# serboRGB.net
KiCad netlist of a schematic drawn in EAGLE
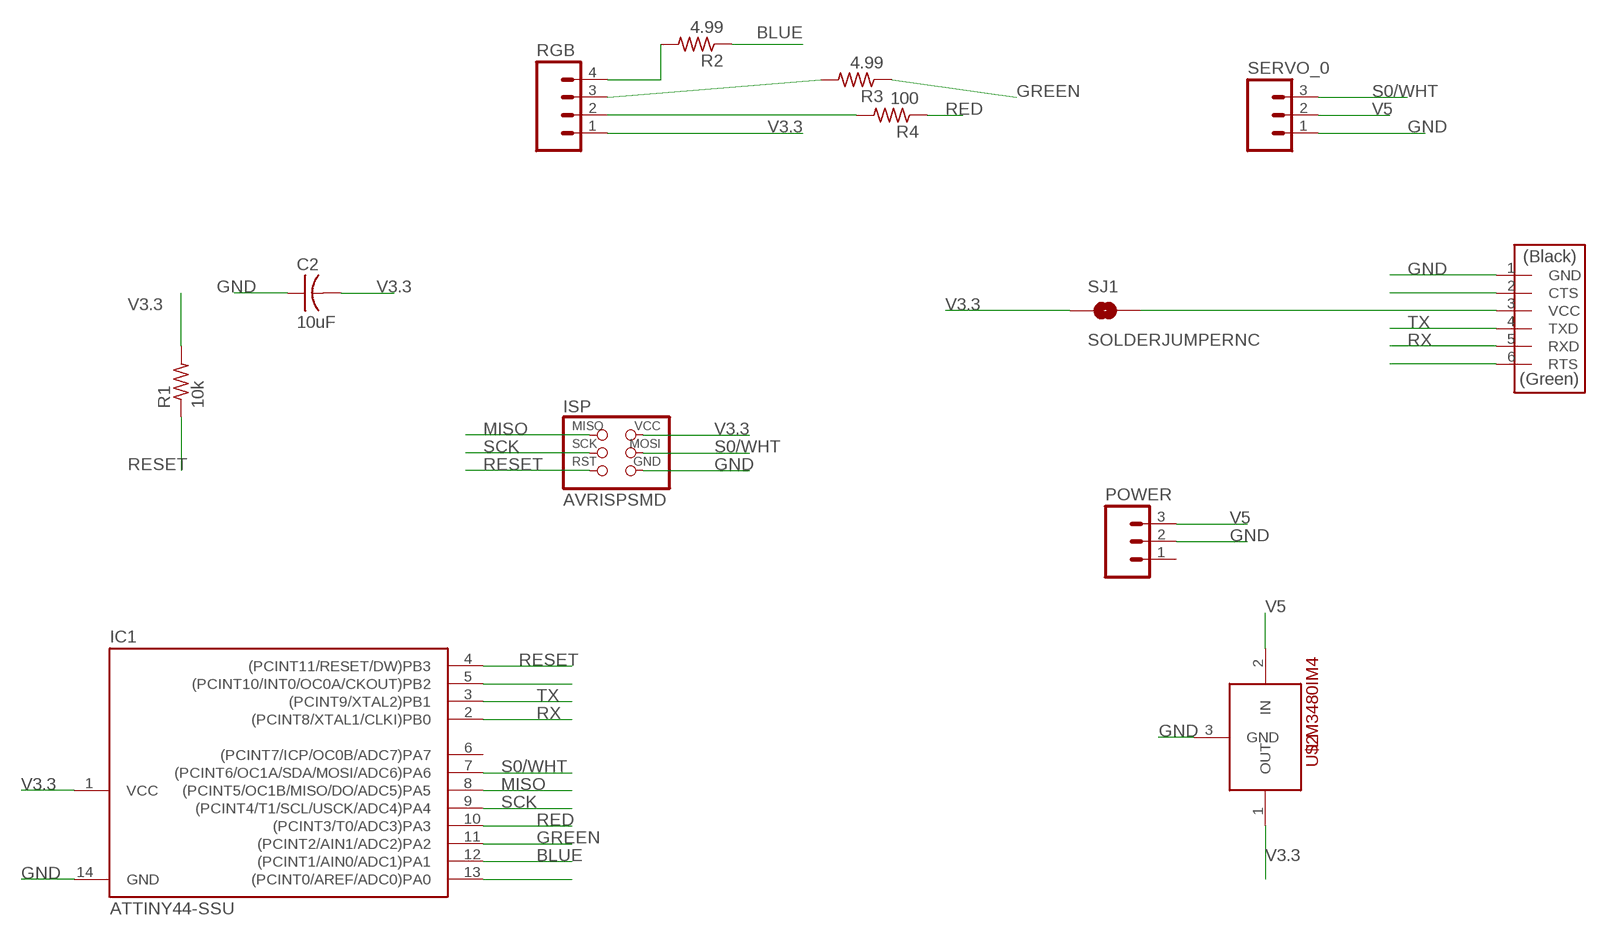
[diagram p0: schematic, sheet 1]

(export (version "E")
  (design (tool "Eeschema 10.0.6"))
  (components
    (comp (ref "C2")
      (value "10uF")
      (footprint "eagle-import:C1206FAB")
      (libsource (lib "eagle-import") (part "CAP-US1206FAB"))
    )
    (comp (ref "IC1")
      (value "ATTINY44-SSU")
      (footprint "eagle-import:SOIC14")
      (libsource (lib "eagle-import") (part "ATTINY44-SSU"))
    )
    (comp (ref "ISP")
      (value "AVRISPSMD")
      (footprint "eagle-import:2X03SMD")
      (libsource (lib "eagle-import") (part "AVRISPSMD"))
    )
    (comp (ref "POWER")
      (value "M03SMD_RA_MALE_POST")
      (footprint "eagle-import:1X03_SMD_RA_MALE_POST")
      (libsource (lib "eagle-import") (part "M03SMD_RA_MALE_POST"))
    )
    (comp (ref "R1")
      (value "10k")
      (footprint "eagle-import:1206")
      (libsource (lib "eagle-import") (part "RESISTOR1206"))
    )
    (comp (ref "R2")
      (value "4.99")
      (footprint "eagle-import:1206")
      (libsource (lib "eagle-import") (part "RESISTOR1206"))
    )
    (comp (ref "R3")
      (value "4.99")
      (footprint "eagle-import:1206")
      (libsource (lib "eagle-import") (part "RESISTOR1206"))
    )
    (comp (ref "R4")
      (value "100")
      (footprint "eagle-import:1206")
      (libsource (lib "eagle-import") (part "RESISTOR1206"))
    )
    (comp (ref "RGB")
      (value "M04SMD")
      (footprint "eagle-import:1X04-SMD")
      (libsource (lib "eagle-import") (part "M04SMD"))
    )
    (comp (ref "SERVO_0")
      (value "M03SMD_RA_MALE_POST")
      (footprint "eagle-import:1X03_SMD_RA_MALE_POST")
      (libsource (lib "eagle-import") (part "M03SMD_RA_MALE_POST"))
    )
    (comp (ref "SJ1")
      (value "SOLDERJUMPERNC")
      (footprint "eagle-import:SJ_2S")
      (libsource (lib "eagle-import") (part "SOLDERJUMPERNC"))
    )
    (comp (ref "U$1")
      (value "FTDI-SMD-HEADER")
      (footprint "eagle-import:1X06SMD")
      (libsource (lib "eagle-import") (part "FTDI-SMD-HEADER"))
    )
    (comp (ref "U$2")
      (value "LM3480IM4")
      (footprint "eagle-import:SOT23-3")
      (libsource (lib "eagle-import") (part "LM3480IM4"))
    )
  )
  (nets
    (net (code "1") (name "/BLUE") (class "Default")
      (node (ref "IC1") (pin "12") (pinfunction "(PCINT1/AIN0/ADC1)PA1_12") (pintype "bidirectional"))
      (node (ref "R2") (pin "1") (pinfunction "1_1") (pintype "passive"))
    )
    (net (code "2") (name "/GND") (class "Default")
      (node (ref "C2") (pin "1") (pinfunction "1_1") (pintype "passive"))
      (node (ref "IC1") (pin "14") (pinfunction "GND_14") (pintype "power_in"))
      (node (ref "ISP") (pin "6") (pinfunction "GND_6") (pintype "passive"))
      (node (ref "POWER") (pin "2") (pinfunction "2_2") (pintype "passive"))
      (node (ref "SERVO_0") (pin "1") (pinfunction "1_1") (pintype "passive"))
      (node (ref "U$1") (pin "1") (pinfunction "GND_1") (pintype "bidirectional"))
      (node (ref "U$2") (pin "3") (pinfunction "GND_3") (pintype "bidirectional"))
    )
    (net (code "3") (name "/GREEN") (class "Default")
      (node (ref "IC1") (pin "11") (pinfunction "(PCINT2/AIN1/ADC2)PA2_11") (pintype "bidirectional"))
      (node (ref "R3") (pin "1") (pinfunction "1_1") (pintype "passive"))
    )
    (net (code "4") (name "/MISO") (class "Default")
      (node (ref "IC1") (pin "8") (pinfunction "(PCINT5/OC1B/MISO/DO/ADC5)PA5_8") (pintype "bidirectional"))
      (node (ref "ISP") (pin "1") (pinfunction "MISO_1") (pintype "passive"))
    )
    (net (code "5") (name "/RED") (class "Default")
      (node (ref "IC1") (pin "10") (pinfunction "(PCINT3/T0/ADC3)PA3_10") (pintype "bidirectional"))
      (node (ref "R4") (pin "1") (pinfunction "1_1") (pintype "passive"))
    )
    (net (code "6") (name "/RESET") (class "Default")
      (node (ref "IC1") (pin "4") (pinfunction "(PCINT11/RESET/DW)PB3_4") (pintype "bidirectional"))
      (node (ref "ISP") (pin "5") (pinfunction "RST_5") (pintype "passive"))
      (node (ref "R1") (pin "1") (pinfunction "1_1") (pintype "passive"))
    )
    (net (code "7") (name "/RX") (class "Default")
      (node (ref "IC1") (pin "2") (pinfunction "(PCINT8/XTAL1/CLKI)PB0_2") (pintype "bidirectional"))
      (node (ref "U$1") (pin "5") (pinfunction "RXD_5") (pintype "bidirectional"))
    )
    (net (code "8") (name "/S0{slash}WHT") (class "Default")
      (node (ref "IC1") (pin "7") (pinfunction "(PCINT6/OC1A/SDA/MOSI/ADC6)PA6_7") (pintype "bidirectional"))
      (node (ref "ISP") (pin "4") (pinfunction "MOSI_4") (pintype "passive"))
      (node (ref "SERVO_0") (pin "3") (pinfunction "3_3") (pintype "passive"))
    )
    (net (code "9") (name "/SCK") (class "Default")
      (node (ref "IC1") (pin "9") (pinfunction "(PCINT4/T1/SCL/USCK/ADC4)PA4_9") (pintype "bidirectional"))
      (node (ref "ISP") (pin "3") (pinfunction "SCK_3") (pintype "passive"))
    )
    (net (code "10") (name "/TX") (class "Default")
      (node (ref "IC1") (pin "3") (pinfunction "(PCINT9/XTAL2)PB1_3") (pintype "bidirectional"))
      (node (ref "U$1") (pin "4") (pinfunction "TXD_4") (pintype "bidirectional"))
    )
    (net (code "11") (name "/V3.3") (class "Default")
      (node (ref "C2") (pin "2") (pinfunction "2_2") (pintype "passive"))
      (node (ref "IC1") (pin "1") (pinfunction "VCC_1") (pintype "power_in"))
      (node (ref "ISP") (pin "2") (pinfunction "VCC_2") (pintype "passive"))
      (node (ref "R1") (pin "2") (pinfunction "2_2") (pintype "passive"))
      (node (ref "RGB") (pin "1") (pinfunction "1_1") (pintype "passive"))
      (node (ref "SJ1") (pin "1") (pinfunction "1_1") (pintype "passive"))
      (node (ref "U$2") (pin "1") (pinfunction "OUT_1") (pintype "bidirectional"))
    )
    (net (code "12") (name "/V5") (class "Default")
      (node (ref "POWER") (pin "3") (pinfunction "3_3") (pintype "passive"))
      (node (ref "SERVO_0") (pin "2") (pinfunction "2_2") (pintype "passive"))
      (node (ref "U$2") (pin "2") (pinfunction "IN_2") (pintype "bidirectional"))
    )
    (net (code "13") (name "Net-(R2-Pad2)") (class "Default")
      (node (ref "R2") (pin "2") (pinfunction "2_2") (pintype "passive"))
      (node (ref "RGB") (pin "4") (pinfunction "4_4") (pintype "passive"))
    )
    (net (code "14") (name "Net-(R3-Pad2)") (class "Default")
      (node (ref "R3") (pin "2") (pinfunction "2_2") (pintype "passive"))
      (node (ref "RGB") (pin "3") (pinfunction "3_3") (pintype "passive"))
    )
    (net (code "15") (name "Net-(R4-Pad2)") (class "Default")
      (node (ref "R4") (pin "2") (pinfunction "2_2") (pintype "passive"))
      (node (ref "RGB") (pin "2") (pinfunction "2_2") (pintype "passive"))
    )
    (net (code "16") (name "Net-(U$1-VCC)") (class "Default")
      (node (ref "SJ1") (pin "2") (pinfunction "2_2") (pintype "passive"))
      (node (ref "U$1") (pin "3") (pinfunction "VCC_3") (pintype "bidirectional"))
    )
    (net (code "17") (name "unconnected-(IC1-(PCINT0{slash}AREF{slash}ADC0)PA0-Pad13)") (class "Default")
      (node (ref "IC1") (pin "13") (pinfunction "(PCINT0/AREF/ADC0)PA0_13") (pintype "bidirectional"))
    )
    (net (code "18") (name "unconnected-(IC1-(PCINT7{slash}ICP{slash}OC0B{slash}ADC7)PA7-Pad6)") (class "Default")
      (node (ref "IC1") (pin "6") (pinfunction "(PCINT7/ICP/OC0B/ADC7)PA7_6") (pintype "bidirectional"))
    )
    (net (code "19") (name "unconnected-(IC1-(PCINT10{slash}INT0{slash}OC0A{slash}CKOUT)PB2-Pad5)") (class "Default")
      (node (ref "IC1") (pin "5") (pinfunction "(PCINT10/INT0/OC0A/CKOUT)PB2_5") (pintype "bidirectional"))
    )
    (net (code "20") (name "unconnected-(POWER-Pad1)") (class "Default")
      (node (ref "POWER") (pin "1") (pinfunction "1_1") (pintype "passive"))
    )
    (net (code "21") (name "unconnected-(U$1-CTS-Pad2)") (class "Default")
      (node (ref "U$1") (pin "2") (pinfunction "CTS_2") (pintype "bidirectional"))
    )
    (net (code "22") (name "unconnected-(U$1-RTS-Pad6)") (class "Default")
      (node (ref "U$1") (pin "6") (pinfunction "RTS_6") (pintype "bidirectional"))
    )
  )
)
